# PowerBike.net
KiCad netlist of a schematic drawn in EAGLE
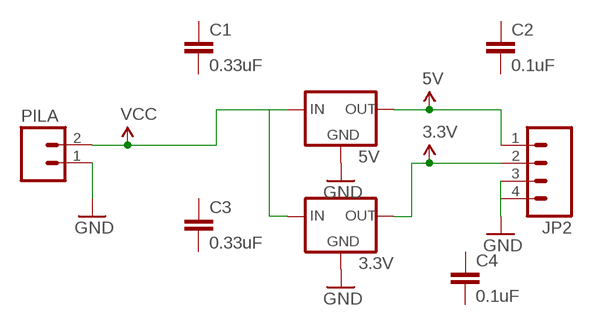
[diagram p0: schematic, sheet 1]

(export (version "E")
  (design (tool "Eeschema 10.0.6"))
  (components
    (comp (ref "3.3V")
      (value "V_REG_78XXSIDE")
      (footprint "eagle-import:78XXL")
      (libsource (lib "eagle-import") (part "V_REG_78XXSIDE"))
    )
    (comp (ref "5V")
      (value "V_REG_78XXSIDE")
      (footprint "eagle-import:78XXL")
      (libsource (lib "eagle-import") (part "V_REG_78XXSIDE"))
    )
    (comp (ref "C1")
      (value "0.33uF")
      (footprint "eagle-import:0603-CAP")
      (libsource (lib "eagle-import") (part "CAP0603-CAP"))
    )
    (comp (ref "C2")
      (value "0.1uF")
      (footprint "eagle-import:0603-CAP")
      (libsource (lib "eagle-import") (part "CAP0603-CAP"))
    )
    (comp (ref "C3")
      (value "0.33uF")
      (footprint "eagle-import:0603-CAP")
      (libsource (lib "eagle-import") (part "CAP0603-CAP"))
    )
    (comp (ref "C4")
      (value "0.1uF")
      (footprint "eagle-import:0603-CAP")
      (libsource (lib "eagle-import") (part "CAP0603-CAP"))
    )
    (comp (ref "JP2")
      (value "M04LOCK_LONGPADS")
      (footprint "eagle-import:1X04_LOCK_LONGPADS")
      (libsource (lib "eagle-import") (part "M04LOCK_LONGPADS"))
    )
    (comp (ref "PILA")
      (value "M02LOCK_LONGPADS")
      (footprint "eagle-import:1X02_LOCK_LONGPADS")
      (libsource (lib "eagle-import") (part "M02LOCK_LONGPADS"))
    )
  )
  (nets
    (net (code "1") (name "3.3V") (class "Default")
      (node (ref "3.3V") (pin "OUT") (pinfunction "OUT_OUT") (pintype "output"))
      (node (ref "JP2") (pin "2") (pinfunction "2_2") (pintype "passive"))
    )
    (net (code "2") (name "5V") (class "Default")
      (node (ref "5V") (pin "OUT") (pinfunction "OUT_OUT") (pintype "output"))
      (node (ref "JP2") (pin "1") (pinfunction "1_1") (pintype "passive"))
    )
    (net (code "3") (name "GND") (class "Default")
      (node (ref "3.3V") (pin "GND") (pinfunction "GND_GND") (pintype "input"))
      (node (ref "5V") (pin "GND") (pinfunction "GND_GND") (pintype "input"))
      (node (ref "JP2") (pin "3") (pinfunction "3_3") (pintype "passive"))
      (node (ref "JP2") (pin "4") (pinfunction "4_4") (pintype "passive"))
      (node (ref "PILA") (pin "1") (pinfunction "1_1") (pintype "passive"))
    )
    (net (code "4") (name "VCC") (class "Default")
      (node (ref "3.3V") (pin "IN") (pinfunction "IN_IN") (pintype "input"))
      (node (ref "5V") (pin "IN") (pinfunction "IN_IN") (pintype "input"))
      (node (ref "PILA") (pin "2") (pinfunction "2_2") (pintype "passive"))
    )
    (net (code "5") (name "unconnected-(C1-Pad1)") (class "Default")
      (node (ref "C1") (pin "1") (pinfunction "1_1") (pintype "passive"))
    )
    (net (code "6") (name "unconnected-(C1-Pad2)") (class "Default")
      (node (ref "C1") (pin "2") (pinfunction "2_2") (pintype "passive"))
    )
    (net (code "7") (name "unconnected-(C2-Pad1)") (class "Default")
      (node (ref "C2") (pin "1") (pinfunction "1_1") (pintype "passive"))
    )
    (net (code "8") (name "unconnected-(C2-Pad2)") (class "Default")
      (node (ref "C2") (pin "2") (pinfunction "2_2") (pintype "passive"))
    )
    (net (code "9") (name "unconnected-(C3-Pad1)") (class "Default")
      (node (ref "C3") (pin "1") (pinfunction "1_1") (pintype "passive"))
    )
    (net (code "10") (name "unconnected-(C3-Pad2)") (class "Default")
      (node (ref "C3") (pin "2") (pinfunction "2_2") (pintype "passive"))
    )
    (net (code "11") (name "unconnected-(C4-Pad1)") (class "Default")
      (node (ref "C4") (pin "1") (pinfunction "1_1") (pintype "passive"))
    )
    (net (code "12") (name "unconnected-(C4-Pad2)") (class "Default")
      (node (ref "C4") (pin "2") (pinfunction "2_2") (pintype "passive"))
    )
  )
)
